# 1puvodni.net
KiCad netlist of a schematic drawn in EAGLE
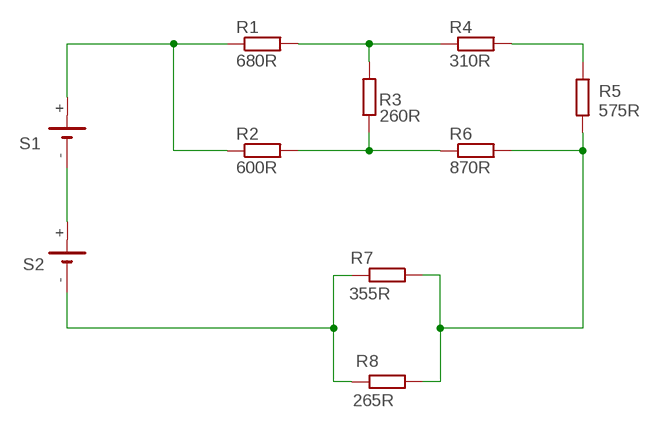
[diagram p0: schematic, sheet 1]

(export (version "E")
  (design (tool "Eeschema 10.0.6"))
  (components
    (comp (ref "R1")
      (value "680R")
      (footprint "eagle-import:0204_7")
      (libsource (lib "eagle-import") (part "R-EU_0204/7"))
    )
    (comp (ref "R2")
      (value "600R")
      (footprint "eagle-import:0204_7")
      (libsource (lib "eagle-import") (part "R-EU_0204/7"))
    )
    (comp (ref "R3")
      (value "260R")
      (footprint "eagle-import:0204_7")
      (libsource (lib "eagle-import") (part "R-EU_0204/7"))
    )
    (comp (ref "R4")
      (value "310R")
      (footprint "eagle-import:0204_7")
      (libsource (lib "eagle-import") (part "R-EU_0204/7"))
    )
    (comp (ref "R5")
      (value "575R")
      (footprint "eagle-import:0204_7")
      (libsource (lib "eagle-import") (part "R-EU_0204/7"))
    )
    (comp (ref "R6")
      (value "870R")
      (footprint "eagle-import:0204_7")
      (libsource (lib "eagle-import") (part "R-EU_0204/7"))
    )
    (comp (ref "R7")
      (value "355R")
      (footprint "eagle-import:0204_7")
      (libsource (lib "eagle-import") (part "R-EU_0204/7"))
    )
    (comp (ref "R8")
      (value "265R")
      (footprint "eagle-import:0204_7")
      (libsource (lib "eagle-import") (part "R-EU_0204/7"))
    )
    (comp (ref "S1")
      (value "135V")
      (footprint "eagle-import:CH291-1220LF")
      (libsource (lib "eagle-import") (part "CH291-1220LF"))
    )
    (comp (ref "S2")
      (value "85V")
      (footprint "eagle-import:CH291-1220LF")
      (libsource (lib "eagle-import") (part "CH291-1220LF"))
    )
  )
  (nets
    (net (code "1") (name "Net-(R1-Pad1)") (class "Default")
      (node (ref "R1") (pin "1") (pinfunction "1_1") (pintype "passive"))
      (node (ref "R2") (pin "1") (pinfunction "1_1") (pintype "passive"))
      (node (ref "S1") (pin "+") (pinfunction "+_+") (pintype "passive"))
    )
    (net (code "2") (name "Net-(R1-Pad2)") (class "Default")
      (node (ref "R1") (pin "2") (pinfunction "2_2") (pintype "passive"))
      (node (ref "R3") (pin "2") (pinfunction "2_2") (pintype "passive"))
      (node (ref "R4") (pin "1") (pinfunction "1_1") (pintype "passive"))
    )
    (net (code "3") (name "Net-(R2-Pad2)") (class "Default")
      (node (ref "R2") (pin "2") (pinfunction "2_2") (pintype "passive"))
      (node (ref "R3") (pin "1") (pinfunction "1_1") (pintype "passive"))
      (node (ref "R6") (pin "1") (pinfunction "1_1") (pintype "passive"))
    )
    (net (code "4") (name "Net-(R4-Pad2)") (class "Default")
      (node (ref "R4") (pin "2") (pinfunction "2_2") (pintype "passive"))
      (node (ref "R5") (pin "1") (pinfunction "1_1") (pintype "passive"))
    )
    (net (code "5") (name "Net-(R5-Pad2)") (class "Default")
      (node (ref "R5") (pin "2") (pinfunction "2_2") (pintype "passive"))
      (node (ref "R6") (pin "2") (pinfunction "2_2") (pintype "passive"))
      (node (ref "R7") (pin "1") (pinfunction "1_1") (pintype "passive"))
      (node (ref "R8") (pin "1") (pinfunction "1_1") (pintype "passive"))
    )
    (net (code "6") (name "Net-(R7-Pad2)") (class "Default")
      (node (ref "R7") (pin "2") (pinfunction "2_2") (pintype "passive"))
      (node (ref "R8") (pin "2") (pinfunction "2_2") (pintype "passive"))
      (node (ref "S2") (pin "-") (pinfunction "-_-") (pintype "passive"))
    )
    (net (code "7") (name "Net-(S1-Pad-)") (class "Default")
      (node (ref "S1") (pin "-") (pinfunction "-_-") (pintype "passive"))
      (node (ref "S2") (pin "+") (pinfunction "+_+") (pintype "passive"))
    )
  )
)
